# PATHOS_ControllerBoardInterface.net
KiCad netlist of a schematic drawn in Altium Designer
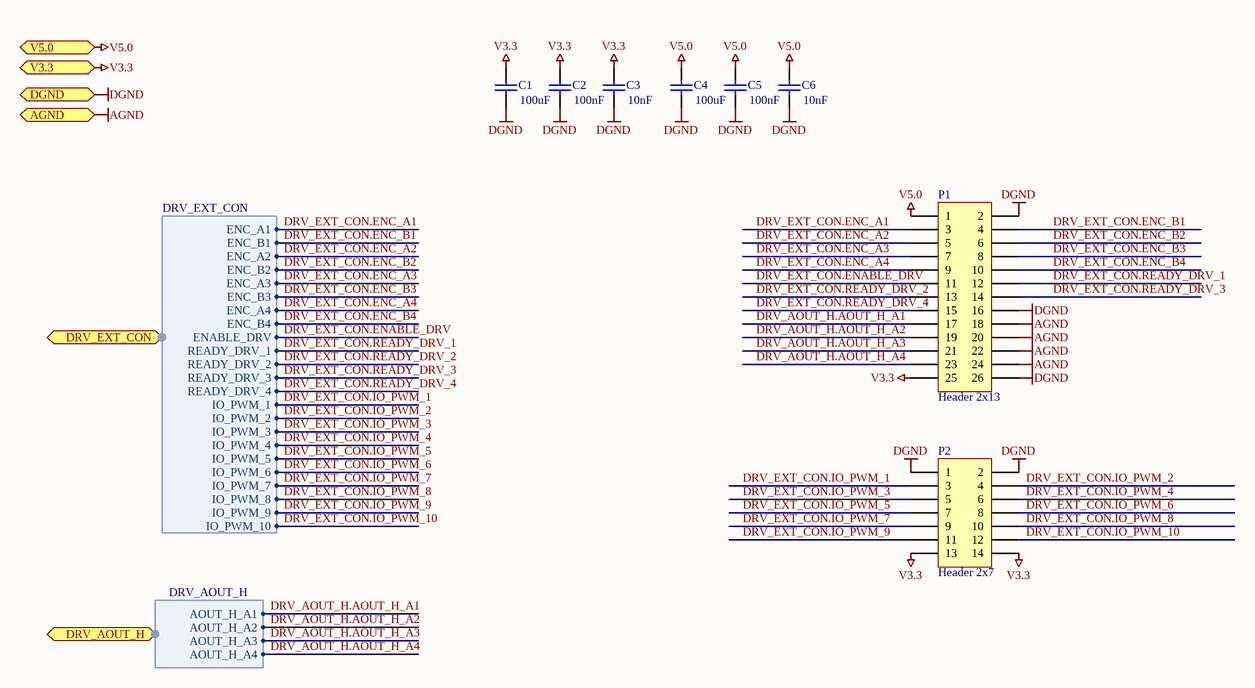
[diagram p0: PATHOS_ControllerBoardInterface.SchDoc]

(export (version "E")
  (design (tool "Eeschema 10.0.6"))
  (components
    (comp (ref "C1")
      (value "100uF")
      (footprint "1812")
      (description "Capacitor")
      (fields (field (name "Comment") "Cap") (field (name "PUBLISHER") "Altium Limited"))
      (libsource (lib "Miscellaneous Devices") (part "Cap"))
    )
    (comp (ref "C2")
      (value "100nF")
      (footprint "0603_3D")
      (description "Capacitor")
      (fields (field (name "Comment") "Cap") (field (name "PUBLISHER") "Altium Limited"))
      (libsource (lib "Miscellaneous Devices") (part "Cap"))
    )
    (comp (ref "C3")
      (value "10nF")
      (footprint "0603_3D")
      (description "Capacitor")
      (fields (field (name "Comment") "Cap") (field (name "PUBLISHER") "Altium Limited"))
      (libsource (lib "Miscellaneous Devices") (part "Cap"))
    )
    (comp (ref "C4")
      (value "100uF")
      (footprint "1812")
      (description "Capacitor")
      (fields (field (name "Comment") "Cap") (field (name "PUBLISHER") "Altium Limited"))
      (libsource (lib "Miscellaneous Devices") (part "Cap"))
    )
    (comp (ref "C5")
      (value "100nF")
      (footprint "0603_3D")
      (description "Capacitor")
      (fields (field (name "Comment") "Cap") (field (name "PUBLISHER") "Altium Limited"))
      (libsource (lib "Miscellaneous Devices") (part "Cap"))
    )
    (comp (ref "C6")
      (value "10nF")
      (footprint "0603_3D")
      (description "Capacitor")
      (fields (field (name "Comment") "Cap") (field (name "PUBLISHER") "Altium Limited"))
      (libsource (lib "Miscellaneous Devices") (part "Cap"))
    )
    (comp (ref "P1")
      (value "Header 2x13")
      (footprint "Wannenstecker26Pol")
      (description "Header, 13-Pin, Dual row")
      (fields (field (name "PUBLISHER") "Altium Limited"))
      (libsource (lib "inf") (part "Header 2x13"))
    )
    (comp (ref "P2")
      (value "Header 2x7")
      (footprint "Wannenstecker14Pol")
      (description "Header, 7-Pin, Dual row")
      (fields (field (name "PUBLISHER") "Altium Limited"))
      (libsource (lib "inf") (part "Header 2x7"))
    )
  )
  (nets
    (net (code "3") (name "/DRV_AOUT_H.AOUT_H_A1") (class "Default")
      (node (ref "P1") (pin "17") (pinfunction "17_17") (pintype "passive"))
    )
    (net (code "4") (name "/DRV_AOUT_H.AOUT_H_A2") (class "Default")
      (node (ref "P1") (pin "19") (pinfunction "19_19") (pintype "passive"))
    )
    (net (code "5") (name "/DRV_AOUT_H.AOUT_H_A3") (class "Default")
      (node (ref "P1") (pin "21") (pinfunction "21_21") (pintype "passive"))
    )
    (net (code "6") (name "/DRV_AOUT_H.AOUT_H_A4") (class "Default")
      (node (ref "P1") (pin "23") (pinfunction "23_23") (pintype "passive"))
    )
    (net (code "7") (name "/DRV_EXT_CON.ENABLE_DRV") (class "Default")
      (node (ref "P1") (pin "11") (pinfunction "11_11") (pintype "passive"))
    )
    (net (code "8") (name "/DRV_EXT_CON.ENC_A1") (class "Default")
      (node (ref "P1") (pin "3") (pinfunction "3_3") (pintype "passive"))
    )
    (net (code "9") (name "/DRV_EXT_CON.ENC_A2") (class "Default")
      (node (ref "P1") (pin "5") (pinfunction "5_5") (pintype "passive"))
    )
    (net (code "10") (name "/DRV_EXT_CON.ENC_A3") (class "Default")
      (node (ref "P1") (pin "7") (pinfunction "7_7") (pintype "passive"))
    )
    (net (code "11") (name "/DRV_EXT_CON.ENC_A4") (class "Default")
      (node (ref "P1") (pin "9") (pinfunction "9_9") (pintype "passive"))
    )
    (net (code "12") (name "/DRV_EXT_CON.ENC_B1") (class "Default")
      (node (ref "P1") (pin "4") (pinfunction "4_4") (pintype "passive"))
    )
    (net (code "13") (name "/DRV_EXT_CON.ENC_B2") (class "Default")
      (node (ref "P1") (pin "6") (pinfunction "6_6") (pintype "passive"))
    )
    (net (code "14") (name "/DRV_EXT_CON.ENC_B3") (class "Default")
      (node (ref "P1") (pin "8") (pinfunction "8_8") (pintype "passive"))
    )
    (net (code "15") (name "/DRV_EXT_CON.ENC_B4") (class "Default")
      (node (ref "P1") (pin "10") (pinfunction "10_10") (pintype "passive"))
    )
    (net (code "16") (name "/DRV_EXT_CON.IO_PWM_1") (class "Default")
      (node (ref "P2") (pin "3") (pinfunction "3_3") (pintype "passive"))
    )
    (net (code "17") (name "/DRV_EXT_CON.IO_PWM_2") (class "Default")
      (node (ref "P2") (pin "4") (pinfunction "4_4") (pintype "passive"))
    )
    (net (code "18") (name "/DRV_EXT_CON.IO_PWM_3") (class "Default")
      (node (ref "P2") (pin "5") (pinfunction "5_5") (pintype "passive"))
    )
    (net (code "19") (name "/DRV_EXT_CON.IO_PWM_4") (class "Default")
      (node (ref "P2") (pin "6") (pinfunction "6_6") (pintype "passive"))
    )
    (net (code "20") (name "/DRV_EXT_CON.IO_PWM_5") (class "Default")
      (node (ref "P2") (pin "7") (pinfunction "7_7") (pintype "passive"))
    )
    (net (code "21") (name "/DRV_EXT_CON.IO_PWM_6") (class "Default")
      (node (ref "P2") (pin "8") (pinfunction "8_8") (pintype "passive"))
    )
    (net (code "22") (name "/DRV_EXT_CON.IO_PWM_7") (class "Default")
      (node (ref "P2") (pin "9") (pinfunction "9_9") (pintype "passive"))
    )
    (net (code "23") (name "/DRV_EXT_CON.IO_PWM_8") (class "Default")
      (node (ref "P2") (pin "10") (pinfunction "10_10") (pintype "passive"))
    )
    (net (code "24") (name "/DRV_EXT_CON.IO_PWM_9") (class "Default")
      (node (ref "P2") (pin "11") (pinfunction "11_11") (pintype "passive"))
    )
    (net (code "25") (name "/DRV_EXT_CON.IO_PWM_10") (class "Default")
      (node (ref "P2") (pin "12") (pinfunction "12_12") (pintype "passive"))
    )
    (net (code "26") (name "/DRV_EXT_CON.READY_DRV_1") (class "Default")
      (node (ref "P1") (pin "12") (pinfunction "12_12") (pintype "passive"))
    )
    (net (code "27") (name "/DRV_EXT_CON.READY_DRV_2") (class "Default")
      (node (ref "P1") (pin "13") (pinfunction "13_13") (pintype "passive"))
    )
    (net (code "28") (name "/DRV_EXT_CON.READY_DRV_3") (class "Default")
      (node (ref "P1") (pin "14") (pinfunction "14_14") (pintype "passive"))
    )
    (net (code "29") (name "/DRV_EXT_CON.READY_DRV_4") (class "Default")
      (node (ref "P1") (pin "15") (pinfunction "15_15") (pintype "passive"))
    )
    (net (code "32") (name "AGND") (class "Default")
      (node (ref "P1") (pin "18") (pinfunction "18_18") (pintype "passive"))
      (node (ref "P1") (pin "20") (pinfunction "20_20") (pintype "passive"))
      (node (ref "P1") (pin "22") (pinfunction "22_22") (pintype "passive"))
      (node (ref "P1") (pin "24") (pinfunction "24_24") (pintype "passive"))
    )
    (net (code "33") (name "DGND") (class "Default")
      (node (ref "C1") (pin "1") (pinfunction "1_1") (pintype "passive"))
      (node (ref "C2") (pin "1") (pinfunction "1_1") (pintype "passive"))
      (node (ref "C3") (pin "1") (pinfunction "1_1") (pintype "passive"))
      (node (ref "C4") (pin "1") (pinfunction "1_1") (pintype "passive"))
      (node (ref "C5") (pin "1") (pinfunction "1_1") (pintype "passive"))
      (node (ref "C6") (pin "1") (pinfunction "1_1") (pintype "passive"))
      (node (ref "P1") (pin "16") (pinfunction "16_16") (pintype "passive"))
      (node (ref "P1") (pin "2") (pinfunction "2_2") (pintype "passive"))
      (node (ref "P1") (pin "26") (pinfunction "26_26") (pintype "passive"))
      (node (ref "P2") (pin "1") (pinfunction "1_1") (pintype "passive"))
      (node (ref "P2") (pin "2") (pinfunction "2_2") (pintype "passive"))
    )
    (net (code "34") (name "V3.3") (class "Default")
      (node (ref "C1") (pin "2") (pinfunction "2_2") (pintype "passive"))
      (node (ref "C2") (pin "2") (pinfunction "2_2") (pintype "passive"))
      (node (ref "C3") (pin "2") (pinfunction "2_2") (pintype "passive"))
      (node (ref "P1") (pin "25") (pinfunction "25_25") (pintype "passive"))
      (node (ref "P2") (pin "13") (pinfunction "13_13") (pintype "passive"))
      (node (ref "P2") (pin "14") (pinfunction "14_14") (pintype "passive"))
    )
    (net (code "35") (name "V5.0") (class "Default")
      (node (ref "C4") (pin "2") (pinfunction "2_2") (pintype "passive"))
      (node (ref "C5") (pin "2") (pinfunction "2_2") (pintype "passive"))
      (node (ref "C6") (pin "2") (pinfunction "2_2") (pintype "passive"))
      (node (ref "P1") (pin "1") (pinfunction "1_1") (pintype "passive"))
    )
  )
)
